# DoPro_Schematic.net
KiCad netlist of a schematic drawn in Altium Designer
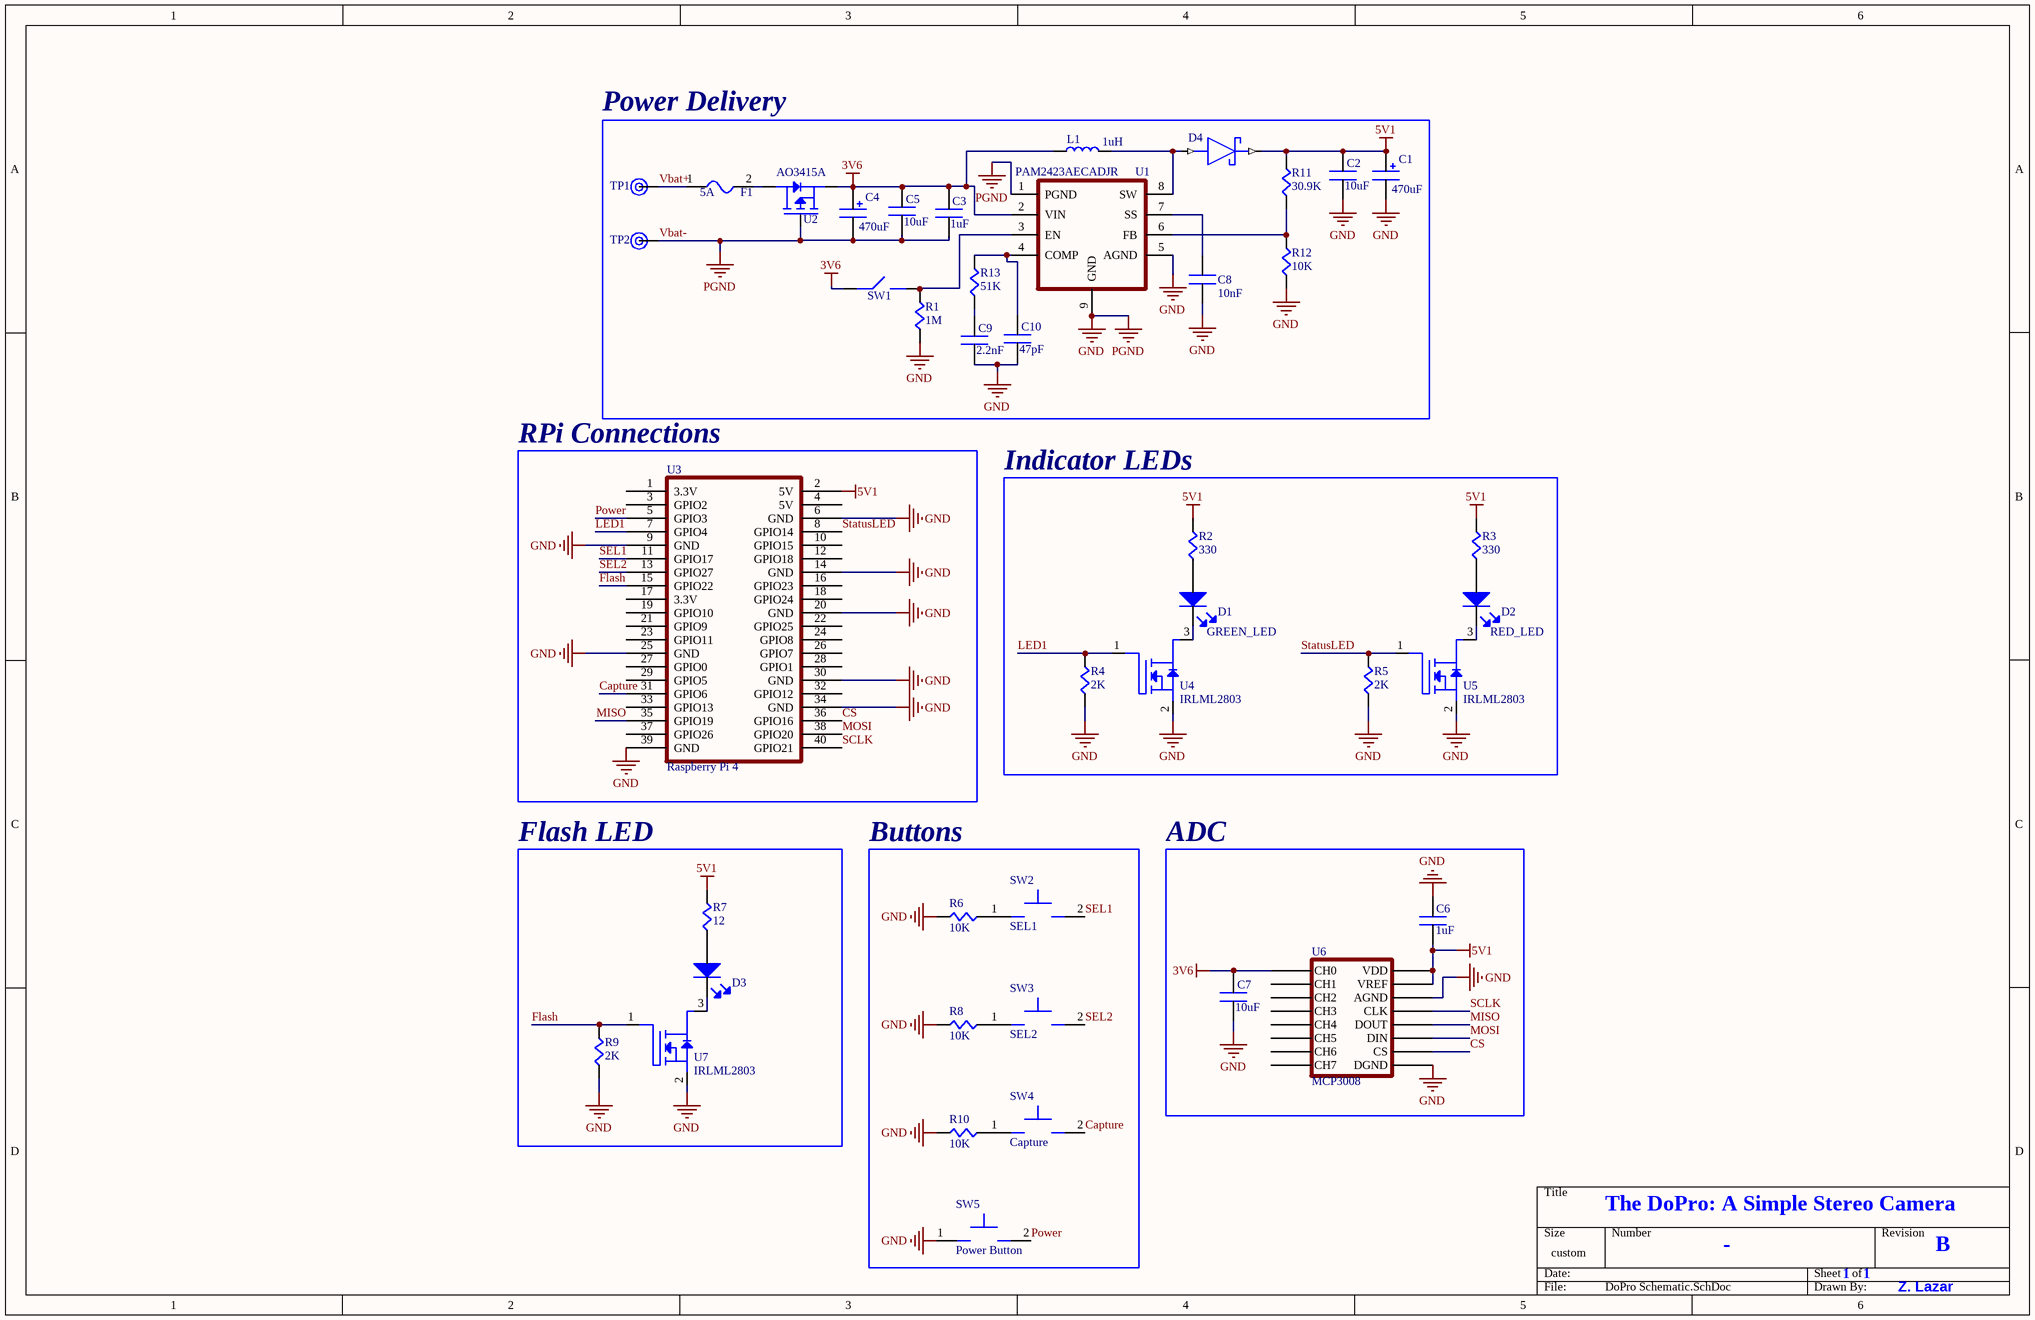
[diagram p0: DoPro Schematic.SchDoc]

(export (version "E")
  (design (tool "Eeschema 10.0.6"))
  (components
    (comp (ref "C1")
      (value "470uF")
      (footprint "SMD_7343")
      (libsource (lib "Zaya Schematic Library") (part "Capacitor_Polarized"))
    )
    (comp (ref "C2")
      (value "10uF")
      (footprint "SMD_0805")
      (libsource (lib "Zaya Schematic Library") (part "Capacitor"))
    )
    (comp (ref "C3")
      (value "1uF")
      (footprint "SMD_0805")
      (libsource (lib "Zaya Schematic Library") (part "Capacitor"))
    )
    (comp (ref "C4")
      (value "470uF")
      (footprint "SMD_7343")
      (libsource (lib "Zaya Schematic Library") (part "Capacitor_Polarized"))
    )
    (comp (ref "C5")
      (value "10uF")
      (footprint "SMD_0805")
      (libsource (lib "Zaya Schematic Library") (part "Capacitor"))
    )
    (comp (ref "C6")
      (value "1uF")
      (footprint "SMD_0805")
      (libsource (lib "Zaya Schematic Library") (part "Capacitor"))
    )
    (comp (ref "C7")
      (value "10uF")
      (footprint "SMD_0805")
      (libsource (lib "Zaya Schematic Library") (part "Capacitor"))
    )
    (comp (ref "C8")
      (value "10nF")
      (footprint "SMD_0805")
      (libsource (lib "Zaya Schematic Library") (part "Capacitor"))
    )
    (comp (ref "C9")
      (value "2.2nF")
      (footprint "SMD_0805")
      (libsource (lib "Zaya Schematic Library") (part "Capacitor"))
    )
    (comp (ref "C10")
      (value "47pF")
      (footprint "SMD_0805")
      (libsource (lib "Zaya Schematic Library") (part "Capacitor"))
    )
    (comp (ref "D1")
      (value "GREEN_LED")
      (footprint "Test_Point_2_62D")
      (libsource (lib "Zaya Schematic Library") (part "LED"))
    )
    (comp (ref "D2")
      (value "RED_LED")
      (footprint "Test_Point_2_62D")
      (libsource (lib "Zaya Schematic Library") (part "LED"))
    )
    (comp (ref "D3")
      (value "MP-1616-1100-50-80")
      (footprint "Test_Point_2_62D")
      (libsource (lib "Zaya Schematic Library") (part "LED"))
    )
    (comp (ref "D4")
      (value "Schottky_Diode")
      (footprint "SMD_SMC_DO-214AB")
      (libsource (lib "Zaya Schematic Library") (part "Schottky_Diode"))
    )
    (comp (ref "F1")
      (value "01550900M")
      (footprint "Littelfuse_154_OMNI-BLOK")
      (description "Holder: 01550900M        Fuse: 0454005.MR")
      (fields (field (name "RATING") "5A"))
      (libsource (lib "Zaya Schematic Library") (part "Fuse_ZAYA"))
    )
    (comp (ref "L1")
      (value "1uH")
      (footprint "Vishay_IHLP-3232DZ-11")
      (description "IHLP3232DZER1R0M11")
      (libsource (lib "Zaya Schematic Library") (part "Inductor"))
    )
    (comp (ref "R1")
      (value "1M")
      (footprint "SMD_0805")
      (libsource (lib "Altium Designer SCH Library") (part "RESISTOR_4_DOUG"))
    )
    (comp (ref "R2")
      (value "330")
      (footprint "SMD_0805")
      (libsource (lib "Altium Designer SCH Library") (part "RESISTOR_4_DOUG"))
    )
    (comp (ref "R3")
      (value "330")
      (footprint "SMD_0805")
      (libsource (lib "Altium Designer SCH Library") (part "RESISTOR_4_DOUG"))
    )
    (comp (ref "R4")
      (value "2K")
      (footprint "SMD_0805")
      (libsource (lib "Altium Designer SCH Library") (part "RESISTOR_4_DOUG"))
    )
    (comp (ref "R5")
      (value "2K")
      (footprint "SMD_0805")
      (libsource (lib "Altium Designer SCH Library") (part "RESISTOR_4_DOUG"))
    )
    (comp (ref "R6")
      (value "10K")
      (footprint "SMD_0805")
      (libsource (lib "Altium Designer SCH Library") (part "RESISTOR_4_DOUG"))
    )
    (comp (ref "R7")
      (value "12")
      (footprint "SMD_0805")
      (libsource (lib "Altium Designer SCH Library") (part "RESISTOR_4_DOUG"))
    )
    (comp (ref "R8")
      (value "10K")
      (footprint "SMD_0805")
      (libsource (lib "Altium Designer SCH Library") (part "RESISTOR_4_DOUG"))
    )
    (comp (ref "R9")
      (value "2K")
      (footprint "SMD_0805")
      (libsource (lib "Altium Designer SCH Library") (part "RESISTOR_4_DOUG"))
    )
    (comp (ref "R10")
      (value "10K")
      (footprint "SMD_0805")
      (libsource (lib "Altium Designer SCH Library") (part "RESISTOR_4_DOUG"))
    )
    (comp (ref "R11")
      (value "30.9K")
      (footprint "SMD_0805")
      (libsource (lib "Altium Designer SCH Library") (part "RESISTOR_4_DOUG"))
    )
    (comp (ref "R12")
      (value "10K")
      (footprint "SMD_0805")
      (libsource (lib "Altium Designer SCH Library") (part "RESISTOR_4_DOUG"))
    )
    (comp (ref "R13")
      (value "51K")
      (footprint "SMD_0805")
      (libsource (lib "Altium Designer SCH Library") (part "RESISTOR_4_DOUG"))
    )
    (comp (ref "SW1")
      (value "Switch")
      (footprint "Test_Point_2_62D")
      (libsource (lib "Zaya Schematic Library") (part "Switch"))
    )
    (comp (ref "SW2")
      (value "SEL1")
      (footprint "Test_Point_2_62D")
      (libsource (lib "Zaya Schematic Library") (part "Button"))
    )
    (comp (ref "SW3")
      (value "SEL2")
      (footprint "Test_Point_2_62D")
      (libsource (lib "Zaya Schematic Library") (part "Button"))
    )
    (comp (ref "SW4")
      (value "Capture")
      (footprint "Test_Point_2_62D")
      (libsource (lib "Zaya Schematic Library") (part "Button"))
    )
    (comp (ref "SW5")
      (value "Power Button")
      (footprint "Test_Point_2_62D")
      (libsource (lib "Zaya Schematic Library") (part "Button"))
    )
    (comp (ref "TP1")
      (value "Vbat+")
      (footprint "Test_Point_100D")
      (libsource (lib "Zaya Schematic Library") (part "Test_Point"))
    )
    (comp (ref "TP2")
      (value "Vbat-")
      (footprint "Test_Point_100D")
      (libsource (lib "Zaya Schematic Library") (part "Test_Point"))
    )
    (comp (ref "U1")
      (value "PAM2423AECADJR")
      (footprint "SMD_SO-8EP")
      (libsource (lib "Zaya Schematic Library") (part "PAM2423AECADJR"))
    )
    (comp (ref "U2")
      (value "AO3415A")
      (footprint "SMD_SOT-23")
      (libsource (lib "Zaya Schematic Library") (part "AO3415A_ZAYA"))
    )
    (comp (ref "U3")
      (value "Raspberry Pi 4")
      (footprint "RPI_Connections")
      (libsource (lib "Zaya Schematic Library") (part "Raspberry Pi 4"))
    )
    (comp (ref "U4")
      (value "IRLML2803")
      (footprint "SMD_SOT-23")
      (libsource (lib "Zaya Schematic Library") (part "IRLML2803_ZAYA"))
    )
    (comp (ref "U5")
      (value "IRLML2803")
      (footprint "SMD_SOT-23")
      (libsource (lib "Zaya Schematic Library") (part "IRLML2803_ZAYA"))
    )
    (comp (ref "U6")
      (value "MCP3008")
      (footprint "SMD_16-SOIC")
      (libsource (lib "Zaya Schematic Library") (part "MCP3008_ZAYA"))
    )
    (comp (ref "U7")
      (value "IRLML2803")
      (footprint "SMD_SOT-23")
      (libsource (lib "Zaya Schematic Library") (part "IRLML2803_ZAYA"))
    )
  )
  (nets
    (net (code "1") (name "/CS") (class "Default")
      (node (ref "U3") (pin "36") (pinfunction "GPIO16_36") (pintype "passive"))
      (node (ref "U6") (pin "10") (pinfunction "CS_10") (pintype "passive"))
    )
    (net (code "2") (name "/Capture") (class "Default")
      (node (ref "SW4") (pin "2") (pintype "passive"))
      (node (ref "U3") (pin "31") (pinfunction "GPIO6_31") (pintype "passive"))
    )
    (net (code "3") (name "/Flash") (class "Default")
      (node (ref "R9") (pin "1") (pinfunction "1_1") (pintype "passive"))
      (node (ref "U3") (pin "15") (pinfunction "GPIO22_15") (pintype "passive"))
      (node (ref "U7") (pin "1") (pinfunction "G_1") (pintype "passive"))
    )
    (net (code "4") (name "/LED1") (class "Default")
      (node (ref "R4") (pin "1") (pinfunction "1_1") (pintype "passive"))
      (node (ref "U3") (pin "7") (pinfunction "GPIO4_7") (pintype "passive"))
      (node (ref "U4") (pin "1") (pinfunction "G_1") (pintype "passive"))
    )
    (net (code "5") (name "/MISO") (class "Default")
      (node (ref "U3") (pin "35") (pinfunction "GPIO19_35") (pintype "passive"))
      (node (ref "U6") (pin "12") (pinfunction "DOUT_12") (pintype "passive"))
    )
    (net (code "6") (name "/MOSI") (class "Default")
      (node (ref "U3") (pin "38") (pinfunction "GPIO20_38") (pintype "passive"))
      (node (ref "U6") (pin "11") (pinfunction "DIN_11") (pintype "passive"))
    )
    (net (code "7") (name "/Power") (class "Default")
      (node (ref "SW5") (pin "2") (pintype "passive"))
      (node (ref "U3") (pin "5") (pinfunction "GPIO3_5") (pintype "passive"))
    )
    (net (code "8") (name "/SCLK") (class "Default")
      (node (ref "U3") (pin "40") (pinfunction "GPIO21_40") (pintype "passive"))
      (node (ref "U6") (pin "13") (pinfunction "CLK_13") (pintype "passive"))
    )
    (net (code "9") (name "/SEL1") (class "Default")
      (node (ref "SW2") (pin "2") (pintype "passive"))
      (node (ref "U3") (pin "11") (pinfunction "GPIO17_11") (pintype "passive"))
    )
    (net (code "10") (name "/SEL2") (class "Default")
      (node (ref "SW3") (pin "2") (pintype "passive"))
      (node (ref "U3") (pin "13") (pinfunction "GPIO27_13") (pintype "passive"))
    )
    (net (code "11") (name "/StatusLED") (class "Default")
      (node (ref "R5") (pin "1") (pinfunction "1_1") (pintype "passive"))
      (node (ref "U3") (pin "8") (pinfunction "GPIO14_8") (pintype "passive"))
      (node (ref "U5") (pin "1") (pinfunction "G_1") (pintype "passive"))
    )
    (net (code "12") (name "/Vbat+") (class "Default")
      (node (ref "F1") (pin "1") (pinfunction "1_1") (pintype "passive"))
      (node (ref "TP1") (pin "1") (pinfunction "1_1") (pintype "passive"))
    )
    (net (code "13") (name "3V6") (class "Default")
      (node (ref "C3") (pin "1") (pinfunction "1_1") (pintype "passive"))
      (node (ref "C4") (pin "1") (pinfunction "1_1") (pintype "passive"))
      (node (ref "C5") (pin "1") (pinfunction "1_1") (pintype "passive"))
      (node (ref "C7") (pin "1") (pinfunction "1_1") (pintype "passive"))
      (node (ref "L1") (pin "1") (pinfunction "1_1") (pintype "passive"))
      (node (ref "SW1") (pin "1") (pinfunction "1_1") (pintype "passive"))
      (node (ref "U1") (pin "2") (pinfunction "VIN_2") (pintype "passive"))
      (node (ref "U2") (pin "2") (pinfunction "S_2") (pintype "passive"))
      (node (ref "U6") (pin "1") (pinfunction "CH0_1") (pintype "passive"))
    )
    (net (code "14") (name "5V1") (class "Default")
      (node (ref "C1") (pin "1") (pinfunction "1_1") (pintype "passive"))
      (node (ref "C2") (pin "1") (pinfunction "1_1") (pintype "passive"))
      (node (ref "C6") (pin "2") (pinfunction "2_2") (pintype "passive"))
      (node (ref "D4") (pin "1") (pinfunction "K_1") (pintype "output"))
      (node (ref "R11") (pin "1") (pinfunction "1_1") (pintype "passive"))
      (node (ref "R2") (pin "1") (pinfunction "1_1") (pintype "passive"))
      (node (ref "R3") (pin "1") (pinfunction "1_1") (pintype "passive"))
      (node (ref "R7") (pin "1") (pinfunction "1_1") (pintype "passive"))
      (node (ref "U3") (pin "2") (pinfunction "5V_2") (pintype "passive"))
      (node (ref "U6") (pin "15") (pinfunction "VREF_15") (pintype "passive"))
      (node (ref "U6") (pin "16") (pinfunction "VDD_16") (pintype "passive"))
    )
    (net (code "15") (name "GND") (class "Default")
      (node (ref "C1") (pin "2") (pinfunction "2_2") (pintype "passive"))
      (node (ref "C10") (pin "2") (pinfunction "2_2") (pintype "passive"))
      (node (ref "C2") (pin "2") (pinfunction "2_2") (pintype "passive"))
      (node (ref "C3") (pin "2") (pinfunction "2_2") (pintype "passive"))
      (node (ref "C4") (pin "2") (pinfunction "2_2") (pintype "passive"))
      (node (ref "C5") (pin "2") (pinfunction "2_2") (pintype "passive"))
      (node (ref "C6") (pin "1") (pinfunction "1_1") (pintype "passive"))
      (node (ref "C7") (pin "2") (pinfunction "2_2") (pintype "passive"))
      (node (ref "C8") (pin "2") (pinfunction "2_2") (pintype "passive"))
      (node (ref "C9") (pin "2") (pinfunction "2_2") (pintype "passive"))
      (node (ref "R1") (pin "2") (pinfunction "2_2") (pintype "passive"))
      (node (ref "R10") (pin "1") (pinfunction "1_1") (pintype "passive"))
      (node (ref "R12") (pin "2") (pinfunction "2_2") (pintype "passive"))
      (node (ref "R4") (pin "2") (pinfunction "2_2") (pintype "passive"))
      (node (ref "R5") (pin "2") (pinfunction "2_2") (pintype "passive"))
      (node (ref "R6") (pin "1") (pinfunction "1_1") (pintype "passive"))
      (node (ref "R8") (pin "1") (pinfunction "1_1") (pintype "passive"))
      (node (ref "R9") (pin "2") (pinfunction "2_2") (pintype "passive"))
      (node (ref "SW5") (pin "1") (pintype "passive"))
      (node (ref "TP2") (pin "1") (pinfunction "1_1") (pintype "passive"))
      (node (ref "U1") (pin "1") (pinfunction "PGND_1") (pintype "passive"))
      (node (ref "U1") (pin "5") (pinfunction "AGND_5") (pintype "passive"))
      (node (ref "U1") (pin "9") (pinfunction "GND_9") (pintype "passive"))
      (node (ref "U2") (pin "1") (pinfunction "G_1") (pintype "passive"))
      (node (ref "U3") (pin "14") (pinfunction "GND_14") (pintype "passive"))
      (node (ref "U3") (pin "20") (pinfunction "GND_20") (pintype "passive"))
      (node (ref "U3") (pin "25") (pinfunction "GND_25") (pintype "passive"))
      (node (ref "U3") (pin "30") (pinfunction "GND_30") (pintype "passive"))
      (node (ref "U3") (pin "34") (pinfunction "GND_34") (pintype "passive"))
      (node (ref "U3") (pin "39") (pinfunction "GND_39") (pintype "passive"))
      (node (ref "U3") (pin "6") (pinfunction "GND_6") (pintype "passive"))
      (node (ref "U3") (pin "9") (pinfunction "GND_9") (pintype "passive"))
      (node (ref "U4") (pin "2") (pinfunction "S_2") (pintype "passive"))
      (node (ref "U5") (pin "2") (pinfunction "S_2") (pintype "passive"))
      (node (ref "U6") (pin "14") (pinfunction "AGND_14") (pintype "passive"))
      (node (ref "U6") (pin "9") (pinfunction "DGND_9") (pintype "passive"))
      (node (ref "U7") (pin "2") (pinfunction "S_2") (pintype "passive"))
    )
    (net (code "16") (name "Net-(C9-Pad1)") (class "Default")
      (node (ref "C9") (pin "1") (pinfunction "1_1") (pintype "passive"))
      (node (ref "R13") (pin "2") (pinfunction "2_2") (pintype "passive"))
    )
    (net (code "17") (name "Net-(D1-Anode)") (class "Default")
      (node (ref "D1") (pin "ANOD") (pinfunction "Anode_ANOD") (pintype "passive"))
      (node (ref "R2") (pin "2") (pinfunction "2_2") (pintype "passive"))
    )
    (net (code "18") (name "Net-(D1-Cathode)") (class "Default")
      (node (ref "D1") (pin "CATH") (pinfunction "Cathode_CATH") (pintype "passive"))
      (node (ref "U4") (pin "3") (pinfunction "D_3") (pintype "passive"))
    )
    (net (code "19") (name "Net-(D2-Anode)") (class "Default")
      (node (ref "D2") (pin "ANOD") (pinfunction "Anode_ANOD") (pintype "passive"))
      (node (ref "R3") (pin "2") (pinfunction "2_2") (pintype "passive"))
    )
    (net (code "20") (name "Net-(D2-Cathode)") (class "Default")
      (node (ref "D2") (pin "CATH") (pinfunction "Cathode_CATH") (pintype "passive"))
      (node (ref "U5") (pin "3") (pinfunction "D_3") (pintype "passive"))
    )
    (net (code "21") (name "Net-(D3-Anode)") (class "Default")
      (node (ref "D3") (pin "ANOD") (pinfunction "Anode_ANOD") (pintype "passive"))
      (node (ref "R7") (pin "2") (pinfunction "2_2") (pintype "passive"))
    )
    (net (code "22") (name "Net-(D3-Cathode)") (class "Default")
      (node (ref "D3") (pin "CATH") (pinfunction "Cathode_CATH") (pintype "passive"))
      (node (ref "U7") (pin "3") (pinfunction "D_3") (pintype "passive"))
    )
    (net (code "23") (name "Net-(D4-A)") (class "Default")
      (node (ref "D4") (pin "2") (pinfunction "A_2") (pintype "input"))
      (node (ref "L1") (pin "2") (pinfunction "2_2") (pintype "passive"))
      (node (ref "U1") (pin "8") (pinfunction "SW_8") (pintype "passive"))
    )
    (net (code "24") (name "Net-(R6-Pad2)") (class "Default")
      (node (ref "R6") (pin "2") (pinfunction "2_2") (pintype "passive"))
      (node (ref "SW2") (pin "1") (pintype "passive"))
    )
    (net (code "25") (name "Net-(R8-Pad2)") (class "Default")
      (node (ref "R8") (pin "2") (pinfunction "2_2") (pintype "passive"))
      (node (ref "SW3") (pin "1") (pintype "passive"))
    )
    (net (code "26") (name "Net-(R10-Pad2)") (class "Default")
      (node (ref "R10") (pin "2") (pinfunction "2_2") (pintype "passive"))
      (node (ref "SW4") (pin "1") (pintype "passive"))
    )
    (net (code "27") (name "Net-(U1-COMP)") (class "Default")
      (node (ref "C10") (pin "1") (pinfunction "1_1") (pintype "passive"))
      (node (ref "R13") (pin "1") (pinfunction "1_1") (pintype "passive"))
      (node (ref "U1") (pin "4") (pinfunction "COMP_4") (pintype "passive"))
    )
    (net (code "28") (name "Net-(U1-EN)") (class "Default")
      (node (ref "R1") (pin "1") (pinfunction "1_1") (pintype "passive"))
      (node (ref "SW1") (pin "2") (pinfunction "2_2") (pintype "passive"))
      (node (ref "U1") (pin "3") (pinfunction "EN_3") (pintype "passive"))
    )
    (net (code "29") (name "Net-(U1-FB)") (class "Default")
      (node (ref "R11") (pin "2") (pinfunction "2_2") (pintype "passive"))
      (node (ref "R12") (pin "1") (pinfunction "1_1") (pintype "passive"))
      (node (ref "U1") (pin "6") (pinfunction "FB_6") (pintype "passive"))
    )
    (net (code "30") (name "Net-(U1-SS)") (class "Default")
      (node (ref "C8") (pin "1") (pinfunction "1_1") (pintype "passive"))
      (node (ref "U1") (pin "7") (pinfunction "SS_7") (pintype "passive"))
    )
    (net (code "31") (name "Net-(U2-D)") (class "Default")
      (node (ref "F1") (pin "2") (pinfunction "2_2") (pintype "passive"))
      (node (ref "U2") (pin "3") (pinfunction "D_3") (pintype "passive"))
    )
    (net (code "32") (name "unconnected-(U3-3.3V-Pad1)") (class "Default")
      (node (ref "U3") (pin "1") (pinfunction "3.3V_1") (pintype "passive"))
    )
    (net (code "33") (name "unconnected-(U3-3.3V-Pad17)") (class "Default")
      (node (ref "U3") (pin "17") (pinfunction "3.3V_17") (pintype "passive"))
    )
    (net (code "34") (name "unconnected-(U3-5V-Pad4)") (class "Default")
      (node (ref "U3") (pin "4") (pinfunction "5V_4") (pintype "passive"))
    )
    (net (code "35") (name "unconnected-(U3-GPIO0-Pad27)") (class "Default")
      (node (ref "U3") (pin "27") (pinfunction "GPIO0_27") (pintype "passive"))
    )
    (net (code "36") (name "unconnected-(U3-GPIO1-Pad28)") (class "Default")
      (node (ref "U3") (pin "28") (pinfunction "GPIO1_28") (pintype "passive"))
    )
    (net (code "37") (name "unconnected-(U3-GPIO2-Pad3)") (class "Default")
      (node (ref "U3") (pin "3") (pinfunction "GPIO2_3") (pintype "passive"))
    )
    (net (code "38") (name "unconnected-(U3-GPIO5-Pad29)") (class "Default")
      (node (ref "U3") (pin "29") (pinfunction "GPIO5_29") (pintype "passive"))
    )
    (net (code "39") (name "unconnected-(U3-GPIO7-Pad26)") (class "Default")
      (node (ref "U3") (pin "26") (pinfunction "GPIO7_26") (pintype "passive"))
    )
    (net (code "40") (name "unconnected-(U3-GPIO8-Pad24)") (class "Default")
      (node (ref "U3") (pin "24") (pinfunction "GPIO8_24") (pintype "passive"))
    )
    (net (code "41") (name "unconnected-(U3-GPIO9-Pad21)") (class "Default")
      (node (ref "U3") (pin "21") (pinfunction "GPIO9_21") (pintype "passive"))
    )
    (net (code "42") (name "unconnected-(U3-GPIO10-Pad19)") (class "Default")
      (node (ref "U3") (pin "19") (pinfunction "GPIO10_19") (pintype "passive"))
    )
    (net (code "43") (name "unconnected-(U3-GPIO11-Pad23)") (class "Default")
      (node (ref "U3") (pin "23") (pinfunction "GPIO11_23") (pintype "passive"))
    )
    (net (code "44") (name "unconnected-(U3-GPIO12-Pad32)") (class "Default")
      (node (ref "U3") (pin "32") (pinfunction "GPIO12_32") (pintype "passive"))
    )
    (net (code "45") (name "unconnected-(U3-GPIO13-Pad33)") (class "Default")
      (node (ref "U3") (pin "33") (pinfunction "GPIO13_33") (pintype "passive"))
    )
    (net (code "46") (name "unconnected-(U3-GPIO15-Pad10)") (class "Default")
      (node (ref "U3") (pin "10") (pinfunction "GPIO15_10") (pintype "passive"))
    )
    (net (code "47") (name "unconnected-(U3-GPIO18-Pad12)") (class "Default")
      (node (ref "U3") (pin "12") (pinfunction "GPIO18_12") (pintype "passive"))
    )
    (net (code "48") (name "unconnected-(U3-GPIO23-Pad16)") (class "Default")
      (node (ref "U3") (pin "16") (pinfunction "GPIO23_16") (pintype "passive"))
    )
    (net (code "49") (name "unconnected-(U3-GPIO24-Pad18)") (class "Default")
      (node (ref "U3") (pin "18") (pinfunction "GPIO24_18") (pintype "passive"))
    )
    (net (code "50") (name "unconnected-(U3-GPIO25-Pad22)") (class "Default")
      (node (ref "U3") (pin "22") (pinfunction "GPIO25_22") (pintype "passive"))
    )
    (net (code "51") (name "unconnected-(U3-GPIO26-Pad37)") (class "Default")
      (node (ref "U3") (pin "37") (pinfunction "GPIO26_37") (pintype "passive"))
    )
    (net (code "52") (name "unconnected-(U6-CH1-Pad2)") (class "Default")
      (node (ref "U6") (pin "2") (pinfunction "CH1_2") (pintype "passive"))
    )
    (net (code "53") (name "unconnected-(U6-CH2-Pad3)") (class "Default")
      (node (ref "U6") (pin "3") (pinfunction "CH2_3") (pintype "passive"))
    )
    (net (code "54") (name "unconnected-(U6-CH3-Pad4)") (class "Default")
      (node (ref "U6") (pin "4") (pinfunction "CH3_4") (pintype "passive"))
    )
    (net (code "55") (name "unconnected-(U6-CH4-Pad5)") (class "Default")
      (node (ref "U6") (pin "5") (pinfunction "CH4_5") (pintype "passive"))
    )
    (net (code "56") (name "unconnected-(U6-CH5-Pad6)") (class "Default")
      (node (ref "U6") (pin "6") (pinfunction "CH5_6") (pintype "passive"))
    )
    (net (code "57") (name "unconnected-(U6-CH6-Pad7)") (class "Default")
      (node (ref "U6") (pin "7") (pinfunction "CH6_7") (pintype "passive"))
    )
    (net (code "58") (name "unconnected-(U6-CH7-Pad8)") (class "Default")
      (node (ref "U6") (pin "8") (pinfunction "CH7_8") (pintype "passive"))
    )
  )
)
